# LnControlPanel.net
KiCad netlist of a schematic drawn in EAGLE
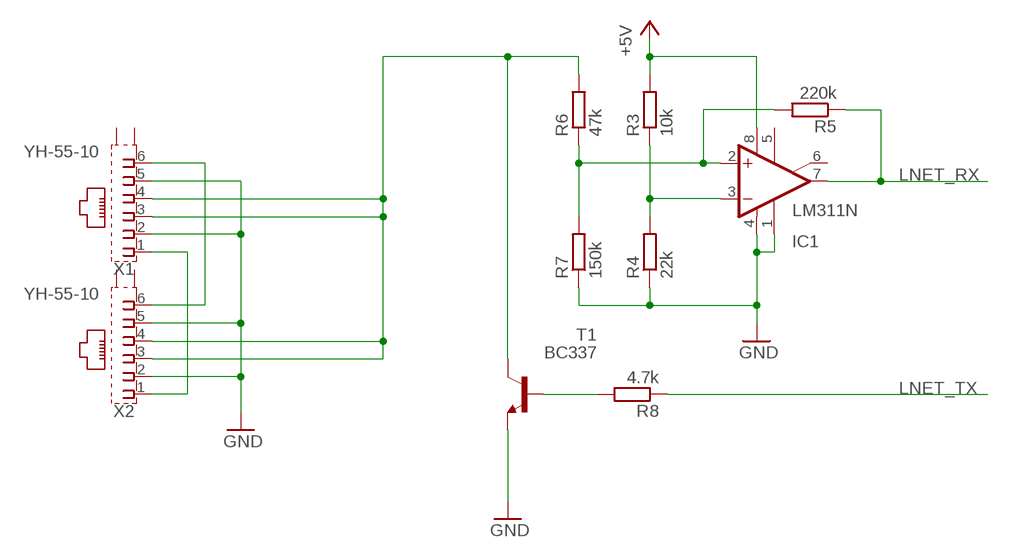
[diagram p0: schematic, sheet 1]
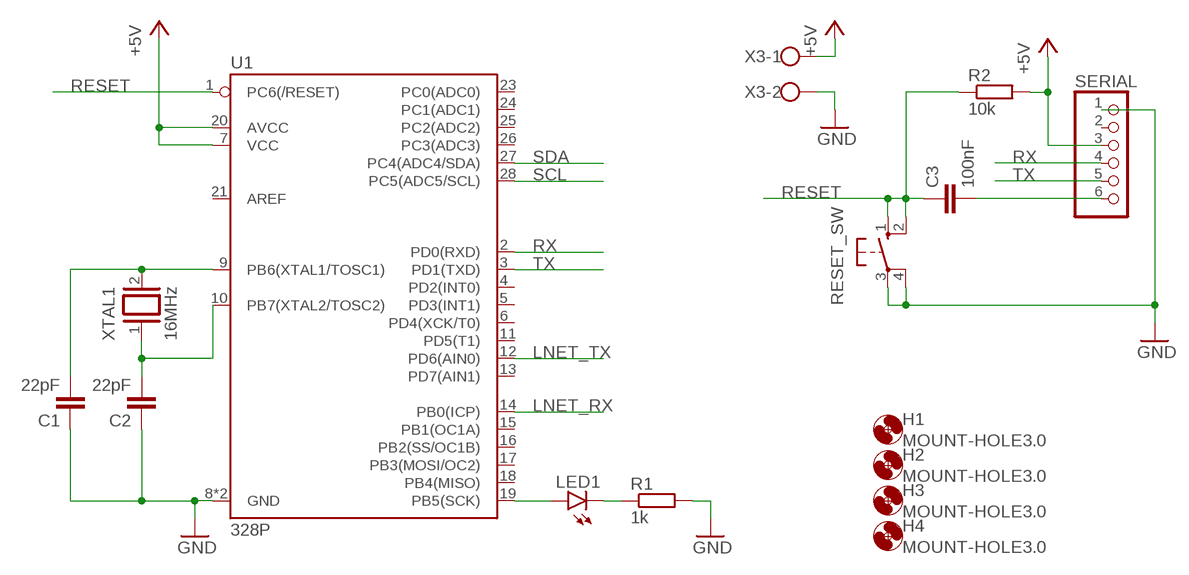
[diagram p1: schematic, sheet 2]
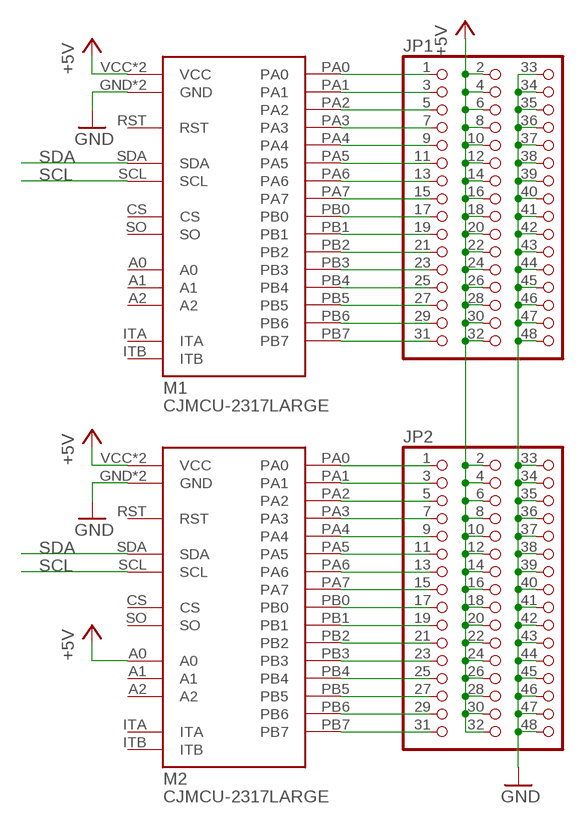
[diagram p2: schematic, sheet 3]

(export (version "E")
  (design (tool "Eeschema 10.0.6"))
  (components
    (comp (ref "JP1")
      (value "PINHD-3X16")
      (footprint "eagle-import:3X16")
      (libsource (lib "eagle-import") (part "PINHD-3X16"))
    )
    (comp (ref "JP2")
      (value "PINHD-3X16")
      (footprint "eagle-import:3X16")
      (libsource (lib "eagle-import") (part "PINHD-3X16"))
    )
    (comp (ref "M1")
      (value "CJMCU-2317LARGE")
      (footprint "eagle-import:CJMCU-2317-PACKAGE2")
      (libsource (lib "eagle-import") (part "CJMCU-2317LARGE"))
    )
    (comp (ref "M2")
      (value "CJMCU-2317LARGE")
      (footprint "eagle-import:CJMCU-2317-PACKAGE2")
      (libsource (lib "eagle-import") (part "CJMCU-2317LARGE"))
    )
    (comp (ref "C1")
      (value "22pF")
      (footprint "eagle-import:C025-025X050")
      (libsource (lib "eagle-import") (part "C-EU025-025X050"))
    )
    (comp (ref "C2")
      (value "22pF")
      (footprint "eagle-import:C025-025X050")
      (libsource (lib "eagle-import") (part "C-EU025-025X050"))
    )
    (comp (ref "C3")
      (value "100nF")
      (footprint "eagle-import:C050-030X075")
      (libsource (lib "eagle-import") (part "C-EU050-030X075"))
    )
    (comp (ref "H1")
      (value "MOUNT-HOLE3.0")
      (footprint "eagle-import:3,0")
      (libsource (lib "eagle-import") (part "MOUNT-HOLE3.0"))
    )
    (comp (ref "H2")
      (value "MOUNT-HOLE3.0")
      (footprint "eagle-import:3,0")
      (libsource (lib "eagle-import") (part "MOUNT-HOLE3.0"))
    )
    (comp (ref "H3")
      (value "MOUNT-HOLE3.0")
      (footprint "eagle-import:3,0")
      (libsource (lib "eagle-import") (part "MOUNT-HOLE3.0"))
    )
    (comp (ref "H4")
      (value "MOUNT-HOLE3.0")
      (footprint "eagle-import:3,0")
      (libsource (lib "eagle-import") (part "MOUNT-HOLE3.0"))
    )
    (comp (ref "LED1")
      (value "LED3MM")
      (footprint "eagle-import:LED3MM")
      (libsource (lib "eagle-import") (part "LED3MM"))
    )
    (comp (ref "R1")
      (value "1k")
      (footprint "eagle-import:0207_2V")
      (libsource (lib "eagle-import") (part "rcl_334_R-EU_0207/2V"))
    )
    (comp (ref "R2")
      (value "10k")
      (footprint "eagle-import:0207_2V")
      (libsource (lib "eagle-import") (part "rcl_334_R-EU_0207/2V"))
    )
    (comp (ref "RESET_SW")
      (value "10-XX")
      (footprint "eagle-import:B3F-10XX")
      (fields (field (name "MPN") "B3F-1000"))
      (libsource (lib "eagle-import") (part "10-XX"))
    )
    (comp (ref "SERIAL")
      (value "PINHD-1X6")
      (footprint "eagle-import:1X06")
      (libsource (lib "eagle-import") (part "PINHD-1X6"))
    )
    (comp (ref "U1")
      (value "328P")
      (footprint "eagle-import:DIP28")
      (libsource (lib "eagle-import") (part "ATMEGA328P_PDIP"))
    )
    (comp (ref "X3")
      (value "W237-102")
      (footprint "eagle-import:W237-102")
      (fields (field (name "MPN") "237-102"))
      (libsource (lib "eagle-import") (part "W237-102"))
    )
    (comp (ref "XTAL1")
      (value "16MHz")
      (footprint "eagle-import:QS")
      (libsource (lib "eagle-import") (part "XTAL/S"))
    )
    (comp (ref "IC1")
      (value "LM311N")
      (footprint "eagle-import:DIL08")
      (libsource (lib "eagle-import") (part "LM311N"))
    )
    (comp (ref "R3")
      (value "10k")
      (footprint "eagle-import:0207_2V")
      (libsource (lib "eagle-import") (part "R-EU_0207/2V"))
    )
    (comp (ref "R4")
      (value "22k")
      (footprint "eagle-import:0207_2V")
      (libsource (lib "eagle-import") (part "R-EU_0207/2V"))
    )
    (comp (ref "R5")
      (value "220k")
      (footprint "eagle-import:0207_2V")
      (libsource (lib "eagle-import") (part "R-EU_0207/2V"))
    )
    (comp (ref "R6")
      (value "47k")
      (footprint "eagle-import:0207_2V")
      (libsource (lib "eagle-import") (part "R-EU_0207/2V"))
    )
    (comp (ref "R7")
      (value "150k")
      (footprint "eagle-import:0207_2V")
      (libsource (lib "eagle-import") (part "R-EU_0207/2V"))
    )
    (comp (ref "R8")
      (value "4.7k")
      (footprint "eagle-import:0207_2V")
      (libsource (lib "eagle-import") (part "R-EU_0207/2V"))
    )
    (comp (ref "T1")
      (value "BC337")
      (footprint "eagle-import:TO92")
      (libsource (lib "eagle-import") (part "BC337"))
    )
    (comp (ref "X1")
      (value "YH-55-10")
      (footprint "eagle-import:YH-55-10")
      (libsource (lib "eagle-import") (part "YH-55-10"))
    )
    (comp (ref "X2")
      (value "YH-55-10")
      (footprint "eagle-import:YH-55-10")
      (libsource (lib "eagle-import") (part "YH-55-10"))
    )
  )
  (nets
    (net (code "1") (name "+5V") (class "Default")
      (node (ref "IC1") (pin "8") (pinfunction "V+_8") (pintype "power_in"))
      (node (ref "JP1") (pin "10") (pinfunction "10_10") (pintype "passive"))
      (node (ref "JP1") (pin "12") (pinfunction "12_12") (pintype "passive"))
      (node (ref "JP1") (pin "14") (pinfunction "14_14") (pintype "passive"))
      (node (ref "JP1") (pin "16") (pinfunction "16_16") (pintype "passive"))
      (node (ref "JP1") (pin "18") (pinfunction "18_18") (pintype "passive"))
      (node (ref "JP1") (pin "2") (pinfunction "2_2") (pintype "passive"))
      (node (ref "JP1") (pin "20") (pinfunction "20_20") (pintype "passive"))
      (node (ref "JP1") (pin "22") (pinfunction "22_22") (pintype "passive"))
      (node (ref "JP1") (pin "24") (pinfunction "24_24") (pintype "passive"))
      (node (ref "JP1") (pin "26") (pinfunction "26_26") (pintype "passive"))
      (node (ref "JP1") (pin "28") (pinfunction "28_28") (pintype "passive"))
      (node (ref "JP1") (pin "30") (pinfunction "30_30") (pintype "passive"))
      (node (ref "JP1") (pin "32") (pinfunction "32_32") (pintype "passive"))
      (node (ref "JP1") (pin "4") (pinfunction "4_4") (pintype "passive"))
      (node (ref "JP1") (pin "6") (pinfunction "6_6") (pintype "passive"))
      (node (ref "JP1") (pin "8") (pinfunction "8_8") (pintype "passive"))
      (node (ref "JP2") (pin "10") (pinfunction "10_10") (pintype "passive"))
      (node (ref "JP2") (pin "12") (pinfunction "12_12") (pintype "passive"))
      (node (ref "JP2") (pin "14") (pinfunction "14_14") (pintype "passive"))
      (node (ref "JP2") (pin "16") (pinfunction "16_16") (pintype "passive"))
      (node (ref "JP2") (pin "18") (pinfunction "18_18") (pintype "passive"))
      (node (ref "JP2") (pin "2") (pinfunction "2_2") (pintype "passive"))
      (node (ref "JP2") (pin "20") (pinfunction "20_20") (pintype "passive"))
      (node (ref "JP2") (pin "22") (pinfunction "22_22") (pintype "passive"))
      (node (ref "JP2") (pin "24") (pinfunction "24_24") (pintype "passive"))
      (node (ref "JP2") (pin "26") (pinfunction "26_26") (pintype "passive"))
      (node (ref "JP2") (pin "28") (pinfunction "28_28") (pintype "passive"))
      (node (ref "JP2") (pin "30") (pinfunction "30_30") (pintype "passive"))
      (node (ref "JP2") (pin "32") (pinfunction "32_32") (pintype "passive"))
      (node (ref "JP2") (pin "4") (pinfunction "4_4") (pintype "passive"))
      (node (ref "JP2") (pin "6") (pinfunction "6_6") (pintype "passive"))
      (node (ref "JP2") (pin "8") (pinfunction "8_8") (pintype "passive"))
      (node (ref "M1") (pin "VCC") (pinfunction "VCC_VCC") (pintype "bidirectional"))
      (node (ref "M1") (pin "VCC_2") (pinfunction "VCC_VCC_2") (pintype "bidirectional"))
      (node (ref "M2") (pin "A0") (pinfunction "A0_A0") (pintype "bidirectional"))
      (node (ref "M2") (pin "VCC") (pinfunction "VCC_VCC") (pintype "bidirectional"))
      (node (ref "M2") (pin "VCC_2") (pinfunction "VCC_VCC_2") (pintype "bidirectional"))
      (node (ref "R2") (pin "2") (pinfunction "2_2") (pintype "passive"))
      (node (ref "R3") (pin "2") (pinfunction "2_2") (pintype "passive"))
      (node (ref "SERIAL") (pin "3") (pinfunction "3_3") (pintype "passive"))
      (node (ref "U1") (pin "20") (pinfunction "AVCC_20") (pintype "bidirectional"))
      (node (ref "U1") (pin "7") (pinfunction "VCC_7") (pintype "bidirectional"))
      (node (ref "X3") (pin "1") (pinfunction "KL_1") (pintype "passive"))
    )
    (net (code "2") (name "GND") (class "Default")
      (node (ref "C1") (pin "1") (pinfunction "1_1") (pintype "passive"))
      (node (ref "C2") (pin "1") (pinfunction "1_1") (pintype "passive"))
      (node (ref "IC1") (pin "1") (pinfunction "GND_1") (pintype "passive"))
      (node (ref "IC1") (pin "4") (pinfunction "V-_4") (pintype "power_in"))
      (node (ref "JP1") (pin "33") (pinfunction "33_33") (pintype "passive"))
      (node (ref "JP1") (pin "34") (pinfunction "34_34") (pintype "passive"))
      (node (ref "JP1") (pin "35") (pinfunction "35_35") (pintype "passive"))
      (node (ref "JP1") (pin "36") (pinfunction "36_36") (pintype "passive"))
      (node (ref "JP1") (pin "37") (pinfunction "37_37") (pintype "passive"))
      (node (ref "JP1") (pin "38") (pinfunction "38_38") (pintype "passive"))
      (node (ref "JP1") (pin "39") (pinfunction "39_39") (pintype "passive"))
      (node (ref "JP1") (pin "40") (pinfunction "40_40") (pintype "passive"))
      (node (ref "JP1") (pin "41") (pinfunction "41_41") (pintype "passive"))
      (node (ref "JP1") (pin "42") (pinfunction "42_42") (pintype "passive"))
      (node (ref "JP1") (pin "43") (pinfunction "43_43") (pintype "passive"))
      (node (ref "JP1") (pin "44") (pinfunction "44_44") (pintype "passive"))
      (node (ref "JP1") (pin "45") (pinfunction "45_45") (pintype "passive"))
      (node (ref "JP1") (pin "46") (pinfunction "46_46") (pintype "passive"))
      (node (ref "JP1") (pin "47") (pinfunction "47_47") (pintype "passive"))
      (node (ref "JP1") (pin "48") (pinfunction "48_48") (pintype "passive"))
      (node (ref "JP2") (pin "33") (pinfunction "33_33") (pintype "passive"))
      (node (ref "JP2") (pin "34") (pinfunction "34_34") (pintype "passive"))
      (node (ref "JP2") (pin "35") (pinfunction "35_35") (pintype "passive"))
      (node (ref "JP2") (pin "36") (pinfunction "36_36") (pintype "passive"))
      (node (ref "JP2") (pin "37") (pinfunction "37_37") (pintype "passive"))
      (node (ref "JP2") (pin "38") (pinfunction "38_38") (pintype "passive"))
      (node (ref "JP2") (pin "39") (pinfunction "39_39") (pintype "passive"))
      (node (ref "JP2") (pin "40") (pinfunction "40_40") (pintype "passive"))
      (node (ref "JP2") (pin "41") (pinfunction "41_41") (pintype "passive"))
      (node (ref "JP2") (pin "42") (pinfunction "42_42") (pintype "passive"))
      (node (ref "JP2") (pin "43") (pinfunction "43_43") (pintype "passive"))
      (node (ref "JP2") (pin "44") (pinfunction "44_44") (pintype "passive"))
      (node (ref "JP2") (pin "45") (pinfunction "45_45") (pintype "passive"))
      (node (ref "JP2") (pin "46") (pinfunction "46_46") (pintype "passive"))
      (node (ref "JP2") (pin "47") (pinfunction "47_47") (pintype "passive"))
      (node (ref "JP2") (pin "48") (pinfunction "48_48") (pintype "passive"))
      (node (ref "M1") (pin "GND") (pinfunction "GND_GND") (pintype "bidirectional"))
      (node (ref "M1") (pin "GND_2") (pinfunction "GND_GND_2") (pintype "bidirectional"))
      (node (ref "M2") (pin "GND") (pinfunction "GND_GND") (pintype "bidirectional"))
      (node (ref "M2") (pin "GND_2") (pinfunction "GND_GND_2") (pintype "bidirectional"))
      (node (ref "R1") (pin "2") (pinfunction "2_2") (pintype "passive"))
      (node (ref "R4") (pin "1") (pinfunction "1_1") (pintype "passive"))
      (node (ref "R7") (pin "1") (pinfunction "1_1") (pintype "passive"))
      (node (ref "RESET_SW") (pin "3") (pinfunction "P_3") (pintype "passive"))
      (node (ref "RESET_SW") (pin "4") (pinfunction "P1_4") (pintype "passive"))
      (node (ref "SERIAL") (pin "1") (pinfunction "1_1") (pintype "passive"))
      (node (ref "T1") (pin "1") (pinfunction "E_1") (pintype "passive"))
      (node (ref "U1") (pin "22") (pinfunction "GND_22") (pintype "bidirectional"))
      (node (ref "U1") (pin "8") (pinfunction "GND_8") (pintype "bidirectional"))
      (node (ref "X1") (pin "2") (pinfunction "2_2") (pintype "passive"))
      (node (ref "X1") (pin "5") (pinfunction "5_5") (pintype "passive"))
      (node (ref "X2") (pin "2") (pinfunction "2_2") (pintype "passive"))
      (node (ref "X2") (pin "5") (pinfunction "5_5") (pintype "passive"))
      (node (ref "X3") (pin "2") (pinfunction "KL_2") (pintype "passive"))
    )
    (net (code "3") (name "LNET_RX") (class "Default")
      (node (ref "IC1") (pin "7") (pinfunction "OUT_7") (pintype "output"))
      (node (ref "R5") (pin "1") (pinfunction "1_1") (pintype "passive"))
      (node (ref "U1") (pin "14") (pinfunction "PB0(ICP)_14") (pintype "bidirectional"))
    )
    (net (code "4") (name "LNET_TX") (class "Default")
      (node (ref "R8") (pin "1") (pinfunction "1_1") (pintype "passive"))
      (node (ref "U1") (pin "12") (pinfunction "PD6(AIN0)_12") (pintype "bidirectional"))
    )
    (net (code "5") (name "Net-(C3-Pad2)") (class "Default")
      (node (ref "C3") (pin "2") (pinfunction "2_2") (pintype "passive"))
      (node (ref "SERIAL") (pin "6") (pinfunction "6_6") (pintype "passive"))
    )
    (net (code "6") (name "Net-(IC1-+IN)") (class "Default")
      (node (ref "IC1") (pin "2") (pinfunction "+IN_2") (pintype "input"))
      (node (ref "R5") (pin "2") (pinfunction "2_2") (pintype "passive"))
      (node (ref "R6") (pin "1") (pinfunction "1_1") (pintype "passive"))
      (node (ref "R7") (pin "2") (pinfunction "2_2") (pintype "passive"))
    )
    (net (code "7") (name "Net-(IC1--IN)") (class "Default")
      (node (ref "IC1") (pin "3") (pinfunction "-IN_3") (pintype "input"))
      (node (ref "R3") (pin "1") (pinfunction "1_1") (pintype "passive"))
      (node (ref "R4") (pin "2") (pinfunction "2_2") (pintype "passive"))
    )
    (net (code "8") (name "Net-(JP1-Pad1)") (class "Default")
      (node (ref "JP1") (pin "1") (pinfunction "1_1") (pintype "passive"))
      (node (ref "M1") (pin "PA0") (pinfunction "PA0_PA0") (pintype "bidirectional"))
    )
    (net (code "9") (name "Net-(JP1-Pad3)") (class "Default")
      (node (ref "JP1") (pin "3") (pinfunction "3_3") (pintype "passive"))
      (node (ref "M1") (pin "PA1") (pinfunction "PA1_PA1") (pintype "bidirectional"))
    )
    (net (code "10") (name "Net-(JP1-Pad5)") (class "Default")
      (node (ref "JP1") (pin "5") (pinfunction "5_5") (pintype "passive"))
      (node (ref "M1") (pin "PA2") (pinfunction "PA2_PA2") (pintype "bidirectional"))
    )
    (net (code "11") (name "Net-(JP1-Pad7)") (class "Default")
      (node (ref "JP1") (pin "7") (pinfunction "7_7") (pintype "passive"))
      (node (ref "M1") (pin "PA3") (pinfunction "PA3_PA3") (pintype "bidirectional"))
    )
    (net (code "12") (name "Net-(JP1-Pad9)") (class "Default")
      (node (ref "JP1") (pin "9") (pinfunction "9_9") (pintype "passive"))
      (node (ref "M1") (pin "PA4") (pinfunction "PA4_PA4") (pintype "bidirectional"))
    )
    (net (code "13") (name "Net-(JP1-Pad11)") (class "Default")
      (node (ref "JP1") (pin "11") (pinfunction "11_11") (pintype "passive"))
      (node (ref "M1") (pin "PA5") (pinfunction "PA5_PA5") (pintype "bidirectional"))
    )
    (net (code "14") (name "Net-(JP1-Pad13)") (class "Default")
      (node (ref "JP1") (pin "13") (pinfunction "13_13") (pintype "passive"))
      (node (ref "M1") (pin "PA6") (pinfunction "PA6_PA6") (pintype "bidirectional"))
    )
    (net (code "15") (name "Net-(JP1-Pad15)") (class "Default")
      (node (ref "JP1") (pin "15") (pinfunction "15_15") (pintype "passive"))
      (node (ref "M1") (pin "PA7") (pinfunction "PA7_PA7") (pintype "bidirectional"))
    )
    (net (code "16") (name "Net-(JP1-Pad17)") (class "Default")
      (node (ref "JP1") (pin "17") (pinfunction "17_17") (pintype "passive"))
      (node (ref "M1") (pin "PB0") (pinfunction "PB0_PB0") (pintype "bidirectional"))
    )
    (net (code "17") (name "Net-(JP1-Pad19)") (class "Default")
      (node (ref "JP1") (pin "19") (pinfunction "19_19") (pintype "passive"))
      (node (ref "M1") (pin "PB1") (pinfunction "PB1_PB1") (pintype "bidirectional"))
    )
    (net (code "18") (name "Net-(JP1-Pad21)") (class "Default")
      (node (ref "JP1") (pin "21") (pinfunction "21_21") (pintype "passive"))
      (node (ref "M1") (pin "PB2") (pinfunction "PB2_PB2") (pintype "bidirectional"))
    )
    (net (code "19") (name "Net-(JP1-Pad23)") (class "Default")
      (node (ref "JP1") (pin "23") (pinfunction "23_23") (pintype "passive"))
      (node (ref "M1") (pin "PB3") (pinfunction "PB3_PB3") (pintype "bidirectional"))
    )
    (net (code "20") (name "Net-(JP1-Pad25)") (class "Default")
      (node (ref "JP1") (pin "25") (pinfunction "25_25") (pintype "passive"))
      (node (ref "M1") (pin "PB4") (pinfunction "PB4_PB4") (pintype "bidirectional"))
    )
    (net (code "21") (name "Net-(JP1-Pad27)") (class "Default")
      (node (ref "JP1") (pin "27") (pinfunction "27_27") (pintype "passive"))
      (node (ref "M1") (pin "PB5") (pinfunction "PB5_PB5") (pintype "bidirectional"))
    )
    (net (code "22") (name "Net-(JP1-Pad29)") (class "Default")
      (node (ref "JP1") (pin "29") (pinfunction "29_29") (pintype "passive"))
      (node (ref "M1") (pin "PB6") (pinfunction "PB6_PB6") (pintype "bidirectional"))
    )
    (net (code "23") (name "Net-(JP1-Pad31)") (class "Default")
      (node (ref "JP1") (pin "31") (pinfunction "31_31") (pintype "passive"))
      (node (ref "M1") (pin "PB7") (pinfunction "PB7_PB7") (pintype "bidirectional"))
    )
    (net (code "24") (name "Net-(JP2-Pad1)") (class "Default")
      (node (ref "JP2") (pin "1") (pinfunction "1_1") (pintype "passive"))
      (node (ref "M2") (pin "PA0") (pinfunction "PA0_PA0") (pintype "bidirectional"))
    )
    (net (code "25") (name "Net-(JP2-Pad3)") (class "Default")
      (node (ref "JP2") (pin "3") (pinfunction "3_3") (pintype "passive"))
      (node (ref "M2") (pin "PA1") (pinfunction "PA1_PA1") (pintype "bidirectional"))
    )
    (net (code "26") (name "Net-(JP2-Pad5)") (class "Default")
      (node (ref "JP2") (pin "5") (pinfunction "5_5") (pintype "passive"))
      (node (ref "M2") (pin "PA2") (pinfunction "PA2_PA2") (pintype "bidirectional"))
    )
    (net (code "27") (name "Net-(JP2-Pad7)") (class "Default")
      (node (ref "JP2") (pin "7") (pinfunction "7_7") (pintype "passive"))
      (node (ref "M2") (pin "PA3") (pinfunction "PA3_PA3") (pintype "bidirectional"))
    )
    (net (code "28") (name "Net-(JP2-Pad9)") (class "Default")
      (node (ref "JP2") (pin "9") (pinfunction "9_9") (pintype "passive"))
      (node (ref "M2") (pin "PA4") (pinfunction "PA4_PA4") (pintype "bidirectional"))
    )
    (net (code "29") (name "Net-(JP2-Pad11)") (class "Default")
      (node (ref "JP2") (pin "11") (pinfunction "11_11") (pintype "passive"))
      (node (ref "M2") (pin "PA5") (pinfunction "PA5_PA5") (pintype "bidirectional"))
    )
    (net (code "30") (name "Net-(JP2-Pad13)") (class "Default")
      (node (ref "JP2") (pin "13") (pinfunction "13_13") (pintype "passive"))
      (node (ref "M2") (pin "PA6") (pinfunction "PA6_PA6") (pintype "bidirectional"))
    )
    (net (code "31") (name "Net-(JP2-Pad15)") (class "Default")
      (node (ref "JP2") (pin "15") (pinfunction "15_15") (pintype "passive"))
      (node (ref "M2") (pin "PA7") (pinfunction "PA7_PA7") (pintype "bidirectional"))
    )
    (net (code "32") (name "Net-(JP2-Pad17)") (class "Default")
      (node (ref "JP2") (pin "17") (pinfunction "17_17") (pintype "passive"))
      (node (ref "M2") (pin "PB0") (pinfunction "PB0_PB0") (pintype "bidirectional"))
    )
    (net (code "33") (name "Net-(JP2-Pad19)") (class "Default")
      (node (ref "JP2") (pin "19") (pinfunction "19_19") (pintype "passive"))
      (node (ref "M2") (pin "PB1") (pinfunction "PB1_PB1") (pintype "bidirectional"))
    )
    (net (code "34") (name "Net-(JP2-Pad21)") (class "Default")
      (node (ref "JP2") (pin "21") (pinfunction "21_21") (pintype "passive"))
      (node (ref "M2") (pin "PB2") (pinfunction "PB2_PB2") (pintype "bidirectional"))
    )
    (net (code "35") (name "Net-(JP2-Pad23)") (class "Default")
      (node (ref "JP2") (pin "23") (pinfunction "23_23") (pintype "passive"))
      (node (ref "M2") (pin "PB3") (pinfunction "PB3_PB3") (pintype "bidirectional"))
    )
    (net (code "36") (name "Net-(JP2-Pad25)") (class "Default")
      (node (ref "JP2") (pin "25") (pinfunction "25_25") (pintype "passive"))
      (node (ref "M2") (pin "PB4") (pinfunction "PB4_PB4") (pintype "bidirectional"))
    )
    (net (code "37") (name "Net-(JP2-Pad27)") (class "Default")
      (node (ref "JP2") (pin "27") (pinfunction "27_27") (pintype "passive"))
      (node (ref "M2") (pin "PB5") (pinfunction "PB5_PB5") (pintype "bidirectional"))
    )
    (net (code "38") (name "Net-(JP2-Pad29)") (class "Default")
      (node (ref "JP2") (pin "29") (pinfunction "29_29") (pintype "passive"))
      (node (ref "M2") (pin "PB6") (pinfunction "PB6_PB6") (pintype "bidirectional"))
    )
    (net (code "39") (name "Net-(JP2-Pad31)") (class "Default")
      (node (ref "JP2") (pin "31") (pinfunction "31_31") (pintype "passive"))
      (node (ref "M2") (pin "PB7") (pinfunction "PB7_PB7") (pintype "bidirectional"))
    )
    (net (code "40") (name "Net-(LED1-C)") (class "Default")
      (node (ref "LED1") (pin "K") (pinfunction "C_K") (pintype "passive"))
      (node (ref "R1") (pin "1") (pinfunction "1_1") (pintype "passive"))
    )
    (net (code "41") (name "Net-(T1-B)") (class "Default")
      (node (ref "R8") (pin "2") (pinfunction "2_2") (pintype "passive"))
      (node (ref "T1") (pin "2") (pinfunction "B_2") (pintype "passive"))
    )
    (net (code "42") (name "Net-(T1-C)") (class "Default")
      (node (ref "R6") (pin "2") (pinfunction "2_2") (pintype "passive"))
      (node (ref "T1") (pin "3") (pinfunction "C_3") (pintype "passive"))
      (node (ref "X1") (pin "3") (pinfunction "3_3") (pintype "passive"))
      (node (ref "X1") (pin "4") (pinfunction "4_4") (pintype "passive"))
      (node (ref "X2") (pin "3") (pinfunction "3_3") (pintype "passive"))
      (node (ref "X2") (pin "4") (pinfunction "4_4") (pintype "passive"))
    )
    (net (code "43") (name "Net-(U1-PB5(SCK))") (class "Default")
      (node (ref "LED1") (pin "A") (pinfunction "A_A") (pintype "passive"))
      (node (ref "U1") (pin "19") (pinfunction "PB5(SCK)_19") (pintype "bidirectional"))
    )
    (net (code "44") (name "Net-(U1-PB6(XTAL1{slash}TOSC1))") (class "Default")
      (node (ref "C1") (pin "2") (pinfunction "2_2") (pintype "passive"))
      (node (ref "U1") (pin "9") (pinfunction "PB6(XTAL1/TOSC1)_9") (pintype "bidirectional"))
      (node (ref "XTAL1") (pin "2") (pinfunction "2_2") (pintype "passive"))
    )
    (net (code "45") (name "Net-(U1-PB7(XTAL2{slash}TOSC2))") (class "Default")
      (node (ref "C2") (pin "2") (pinfunction "2_2") (pintype "passive"))
      (node (ref "U1") (pin "10") (pinfunction "PB7(XTAL2/TOSC2)_10") (pintype "bidirectional"))
      (node (ref "XTAL1") (pin "1") (pinfunction "1_1") (pintype "passive"))
    )
    (net (code "46") (name "Net-(X1-Pad1)") (class "Default")
      (node (ref "X1") (pin "1") (pinfunction "1_1") (pintype "passive"))
      (node (ref "X2") (pin "1") (pinfunction "1_1") (pintype "passive"))
    )
    (net (code "47") (name "Net-(X1-Pad6)") (class "Default")
      (node (ref "X1") (pin "6") (pinfunction "6_6") (pintype "passive"))
      (node (ref "X2") (pin "6") (pinfunction "6_6") (pintype "passive"))
    )
    (net (code "48") (name "RESET") (class "Default")
      (node (ref "C3") (pin "1") (pinfunction "1_1") (pintype "passive"))
      (node (ref "R2") (pin "1") (pinfunction "1_1") (pintype "passive"))
      (node (ref "RESET_SW") (pin "1") (pinfunction "S_1") (pintype "passive"))
      (node (ref "RESET_SW") (pin "2") (pinfunction "S1_2") (pintype "passive"))
      (node (ref "U1") (pin "1") (pinfunction "PC6(/RESET)_1") (pintype "bidirectional"))
    )
    (net (code "49") (name "RX") (class "Default")
      (node (ref "SERIAL") (pin "4") (pinfunction "4_4") (pintype "passive"))
      (node (ref "U1") (pin "2") (pinfunction "PD0(RXD)_2") (pintype "bidirectional"))
    )
    (net (code "50") (name "SCL") (class "Default")
      (node (ref "M1") (pin "SCL") (pinfunction "SCL_SCL") (pintype "bidirectional"))
      (node (ref "M2") (pin "SCL") (pinfunction "SCL_SCL") (pintype "bidirectional"))
      (node (ref "U1") (pin "28") (pinfunction "PC5(ADC5/SCL)_28") (pintype "bidirectional"))
    )
    (net (code "51") (name "SDA") (class "Default")
      (node (ref "M1") (pin "SDA") (pinfunction "SDA_SDA") (pintype "bidirectional"))
      (node (ref "M2") (pin "SDA") (pinfunction "SDA_SDA") (pintype "bidirectional"))
      (node (ref "U1") (pin "27") (pinfunction "PC4(ADC4/SDA)_27") (pintype "bidirectional"))
    )
    (net (code "52") (name "TX") (class "Default")
      (node (ref "SERIAL") (pin "5") (pinfunction "5_5") (pintype "passive"))
      (node (ref "U1") (pin "3") (pinfunction "PD1(TXD)_3") (pintype "bidirectional"))
    )
    (net (code "53") (name "unconnected-(IC1-ON-Pad5)") (class "Default")
      (node (ref "IC1") (pin "5") (pinfunction "ON_5") (pintype "passive"))
    )
    (net (code "54") (name "unconnected-(IC1-ON{slash}STR-Pad6)") (class "Default")
      (node (ref "IC1") (pin "6") (pinfunction "ON/STR_6") (pintype "passive"))
    )
    (net (code "55") (name "unconnected-(M1-PadA0)") (class "Default")
      (node (ref "M1") (pin "A0") (pinfunction "A0_A0") (pintype "bidirectional"))
    )
    (net (code "56") (name "unconnected-(M1-PadA1)") (class "Default")
      (node (ref "M1") (pin "A1") (pinfunction "A1_A1") (pintype "bidirectional"))
    )
    (net (code "57") (name "unconnected-(M1-PadA2)") (class "Default")
      (node (ref "M1") (pin "A2") (pinfunction "A2_A2") (pintype "bidirectional"))
    )
    (net (code "58") (name "unconnected-(M1-PadCS)") (class "Default")
      (node (ref "M1") (pin "CS") (pinfunction "CS_CS") (pintype "bidirectional"))
    )
    (net (code "59") (name "unconnected-(M1-PadITA)") (class "Default")
      (node (ref "M1") (pin "ITA") (pinfunction "ITA_ITA") (pintype "bidirectional"))
    )
    (net (code "60") (name "unconnected-(M1-PadITB)") (class "Default")
      (node (ref "M1") (pin "ITB") (pinfunction "ITB_ITB") (pintype "bidirectional"))
    )
    (net (code "61") (name "unconnected-(M1-PadRST)") (class "Default")
      (node (ref "M1") (pin "RST") (pinfunction "RST_RST") (pintype "bidirectional"))
    )
    (net (code "62") (name "unconnected-(M1-PadSO)") (class "Default")
      (node (ref "M1") (pin "SO") (pinfunction "SO_SO") (pintype "bidirectional"))
    )
    (net (code "63") (name "unconnected-(M2-PadA1)") (class "Default")
      (node (ref "M2") (pin "A1") (pinfunction "A1_A1") (pintype "bidirectional"))
    )
    (net (code "64") (name "unconnected-(M2-PadA2)") (class "Default")
      (node (ref "M2") (pin "A2") (pinfunction "A2_A2") (pintype "bidirectional"))
    )
    (net (code "65") (name "unconnected-(M2-PadCS)") (class "Default")
      (node (ref "M2") (pin "CS") (pinfunction "CS_CS") (pintype "bidirectional"))
    )
    (net (code "66") (name "unconnected-(M2-PadITA)") (class "Default")
      (node (ref "M2") (pin "ITA") (pinfunction "ITA_ITA") (pintype "bidirectional"))
    )
    (net (code "67") (name "unconnected-(M2-PadITB)") (class "Default")
      (node (ref "M2") (pin "ITB") (pinfunction "ITB_ITB") (pintype "bidirectional"))
    )
    (net (code "68") (name "unconnected-(M2-PadRST)") (class "Default")
      (node (ref "M2") (pin "RST") (pinfunction "RST_RST") (pintype "bidirectional"))
    )
    (net (code "69") (name "unconnected-(M2-PadSO)") (class "Default")
      (node (ref "M2") (pin "SO") (pinfunction "SO_SO") (pintype "bidirectional"))
    )
    (net (code "70") (name "unconnected-(SERIAL-Pad2)") (class "Default")
      (node (ref "SERIAL") (pin "2") (pinfunction "2_2") (pintype "passive"))
    )
    (net (code "71") (name "unconnected-(U1-AREF-Pad21)") (class "Default")
      (node (ref "U1") (pin "21") (pinfunction "AREF_21") (pintype "bidirectional"))
    )
    (net (code "72") (name "unconnected-(U1-PB1(OC1A)-Pad15)") (class "Default")
      (node (ref "U1") (pin "15") (pinfunction "PB1(OC1A)_15") (pintype "bidirectional"))
    )
    (net (code "73") (name "unconnected-(U1-PB2(SS{slash}OC1B)-Pad16)") (class "Default")
      (node (ref "U1") (pin "16") (pinfunction "PB2(SS/OC1B)_16") (pintype "bidirectional"))
    )
    (net (code "74") (name "unconnected-(U1-PB3(MOSI{slash}OC2)-Pad17)") (class "Default")
      (node (ref "U1") (pin "17") (pinfunction "PB3(MOSI/OC2)_17") (pintype "bidirectional"))
    )
    (net (code "75") (name "unconnected-(U1-PB4(MISO)-Pad18)") (class "Default")
      (node (ref "U1") (pin "18") (pinfunction "PB4(MISO)_18") (pintype "bidirectional"))
    )
    (net (code "76") (name "unconnected-(U1-PC0(ADC0)-Pad23)") (class "Default")
      (node (ref "U1") (pin "23") (pinfunction "PC0(ADC0)_23") (pintype "bidirectional"))
    )
    (net (code "77") (name "unconnected-(U1-PC1(ADC1)-Pad24)") (class "Default")
      (node (ref "U1") (pin "24") (pinfunction "PC1(ADC1)_24") (pintype "bidirectional"))
    )
    (net (code "78") (name "unconnected-(U1-PC2(ADC2)-Pad25)") (class "Default")
      (node (ref "U1") (pin "25") (pinfunction "PC2(ADC2)_25") (pintype "bidirectional"))
    )
    (net (code "79") (name "unconnected-(U1-PC3(ADC3)-Pad26)") (class "Default")
      (node (ref "U1") (pin "26") (pinfunction "PC3(ADC3)_26") (pintype "bidirectional"))
    )
    (net (code "80") (name "unconnected-(U1-PD2(INT0)-Pad4)") (class "Default")
      (node (ref "U1") (pin "4") (pinfunction "PD2(INT0)_4") (pintype "bidirectional"))
    )
    (net (code "81") (name "unconnected-(U1-PD3(INT1)-Pad5)") (class "Default")
      (node (ref "U1") (pin "5") (pinfunction "PD3(INT1)_5") (pintype "bidirectional"))
    )
    (net (code "82") (name "unconnected-(U1-PD4(XCK{slash}T0)-Pad6)") (class "Default")
      (node (ref "U1") (pin "6") (pinfunction "PD4(XCK/T0)_6") (pintype "bidirectional"))
    )
    (net (code "83") (name "unconnected-(U1-PD5(T1)-Pad11)") (class "Default")
      (node (ref "U1") (pin "11") (pinfunction "PD5(T1)_11") (pintype "bidirectional"))
    )
    (net (code "84") (name "unconnected-(U1-PD7(AIN1)-Pad13)") (class "Default")
      (node (ref "U1") (pin "13") (pinfunction "PD7(AIN1)_13") (pintype "bidirectional"))
    )
    (net (code "85") (name "unconnected-(X1-S-PadS1)") (class "Default")
      (node (ref "X1") (pin "S1") (pinfunction "S_S1") (pintype "passive"))
    )
    (net (code "86") (name "unconnected-(X1-S-PadS2)") (class "Default")
      (node (ref "X1") (pin "S2") (pinfunction "S_S2") (pintype "passive"))
    )
    (net (code "87") (name "unconnected-(X2-S-PadS1)") (class "Default")
      (node (ref "X2") (pin "S1") (pinfunction "S_S1") (pintype "passive"))
    )
    (net (code "88") (name "unconnected-(X2-S-PadS2)") (class "Default")
      (node (ref "X2") (pin "S2") (pinfunction "S_S2") (pintype "passive"))
    )
  )
)
